# nanoHC06Rx.net
KiCad netlist of a schematic drawn in EAGLE
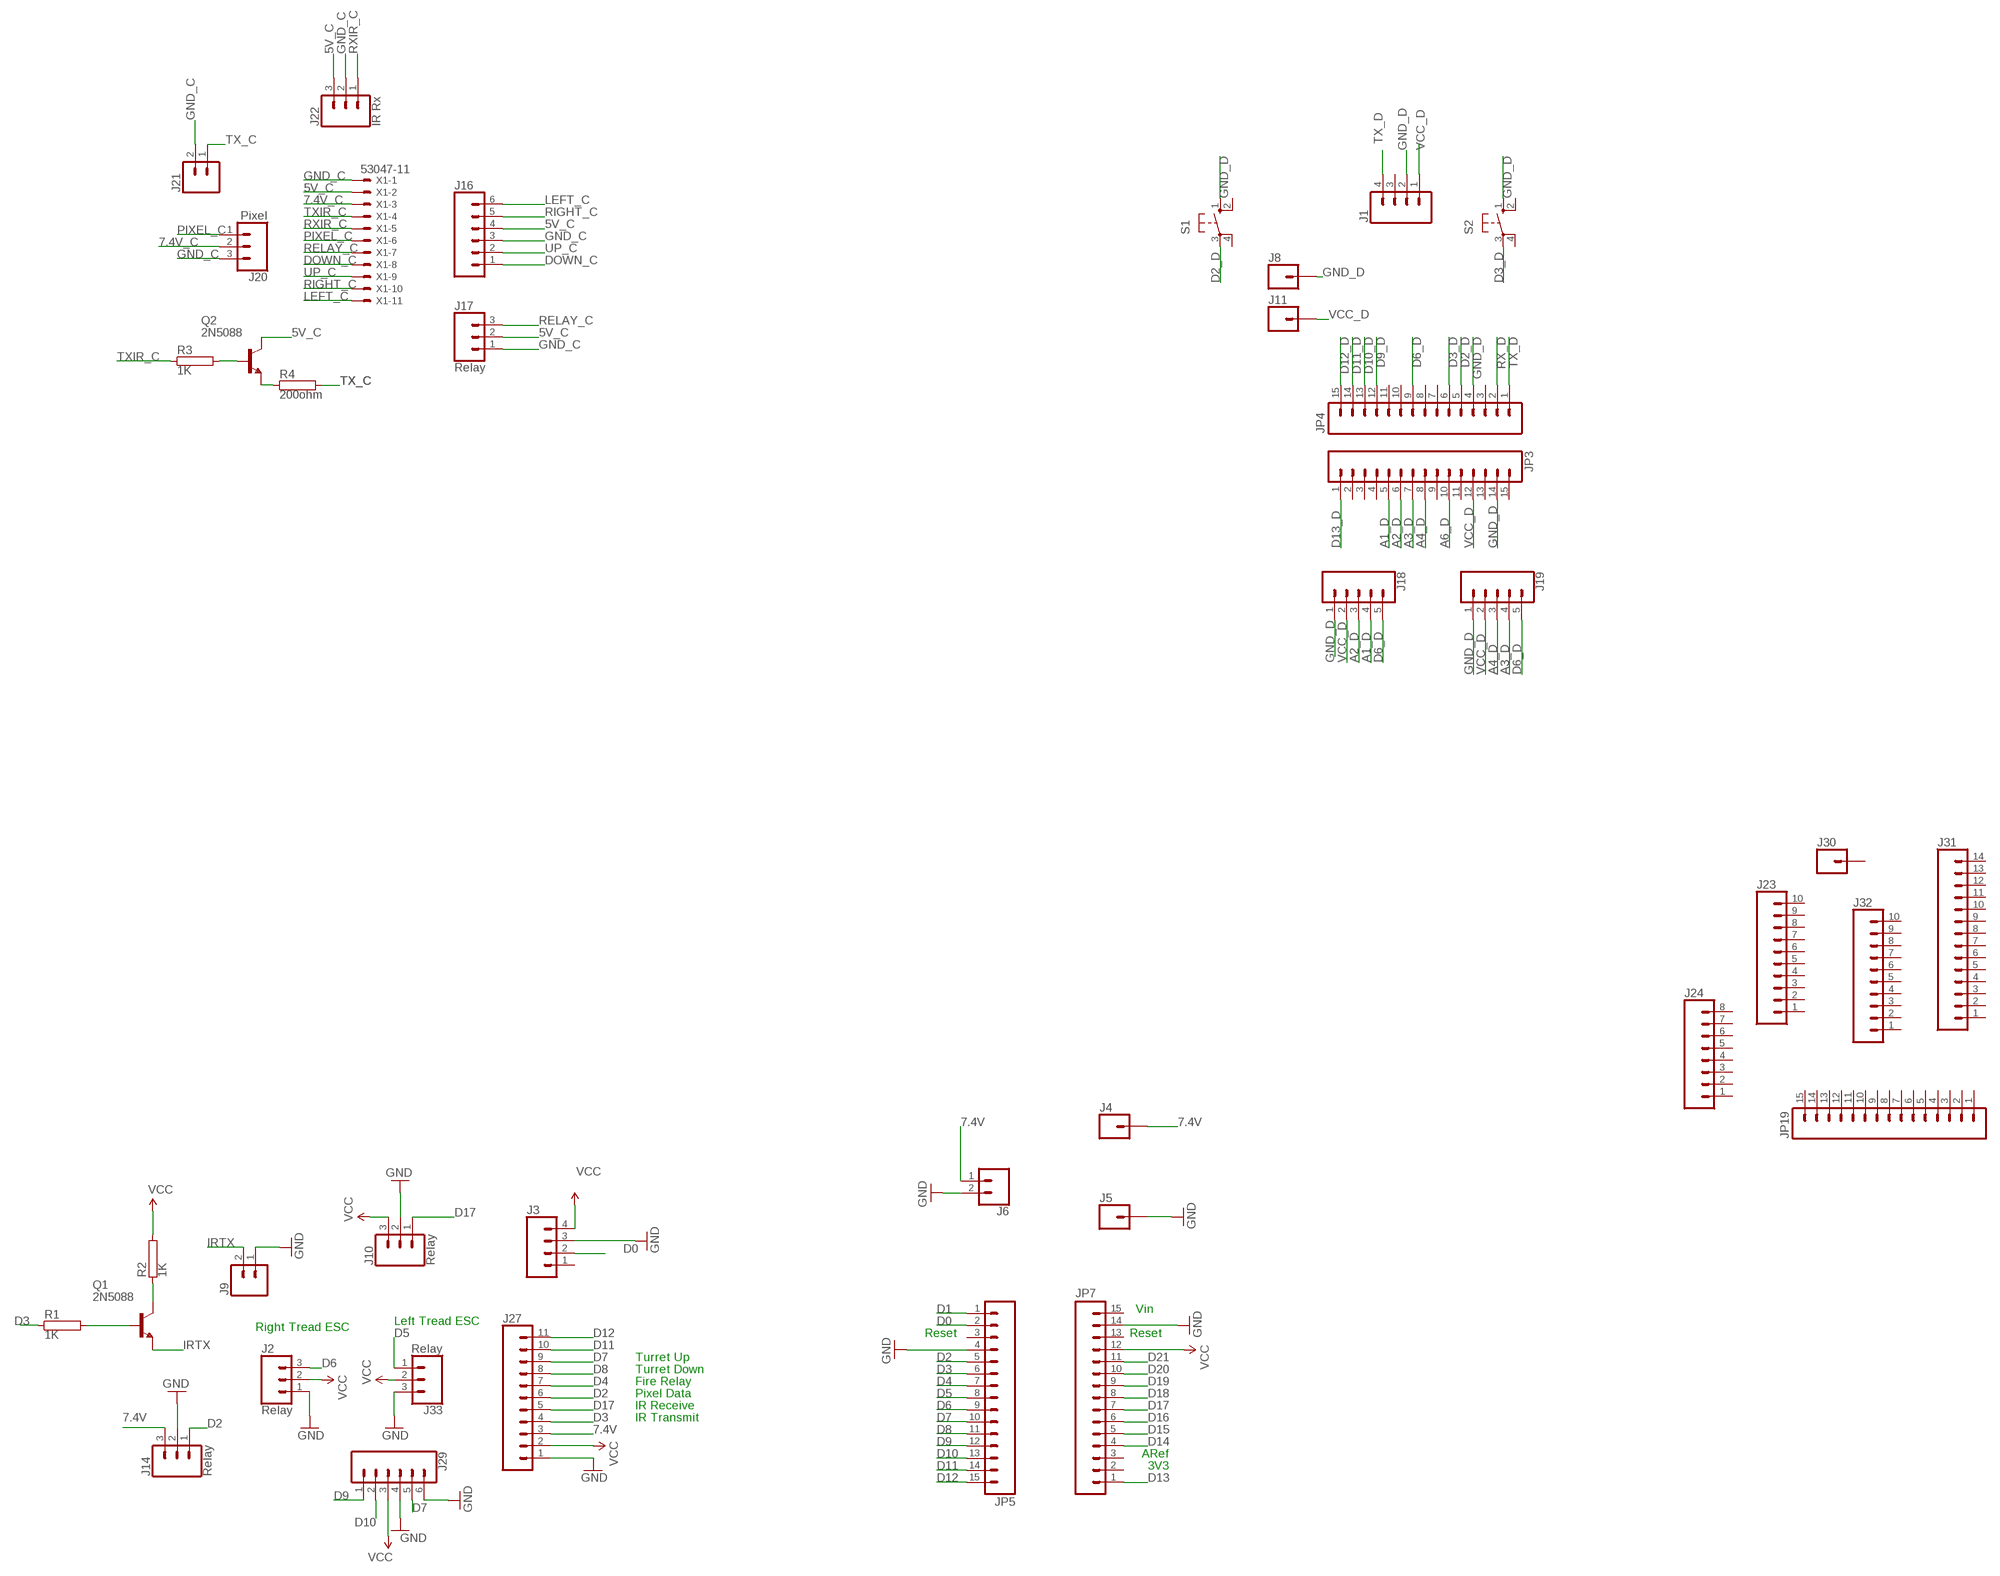
[diagram p0: schematic, sheet 1]

(export (version "E")
  (design (tool "Eeschema 10.0.6"))
  (components
    (comp (ref "J1")
      (value "CONN_04")
      (footprint "eagle-import:1X04")
      (libsource (lib "eagle-import") (part "SparkFun-Connectors_513_CONN_04"))
    )
    (comp (ref "J2")
      (value "Relay")
      (footprint "eagle-import:1X03")
      (libsource (lib "eagle-import") (part "CONN_03"))
    )
    (comp (ref "J3")
      (value "CONN_04")
      (footprint "eagle-import:1X04")
      (libsource (lib "eagle-import") (part "CONN_04"))
    )
    (comp (ref "J4")
      (value "CONN_01")
      (footprint "eagle-import:1X01")
      (libsource (lib "eagle-import") (part "CONN_01"))
    )
    (comp (ref "J5")
      (value "CONN_01")
      (footprint "eagle-import:1X01")
      (libsource (lib "eagle-import") (part "CONN_01"))
    )
    (comp (ref "J6")
      (value "CONN_02")
      (footprint "eagle-import:1X02")
      (libsource (lib "eagle-import") (part "CONN_02"))
    )
    (comp (ref "J8")
      (value "CONN_01")
      (footprint "eagle-import:1X01")
      (libsource (lib "eagle-import") (part "CONN_01"))
    )
    (comp (ref "J9")
      (value "CONN_02")
      (footprint "eagle-import:1X02")
      (libsource (lib "eagle-import") (part "CONN_02"))
    )
    (comp (ref "J10")
      (value "Relay")
      (footprint "eagle-import:1X03")
      (libsource (lib "eagle-import") (part "CONN_03"))
    )
    (comp (ref "J11")
      (value "CONN_01")
      (footprint "eagle-import:1X01")
      (libsource (lib "eagle-import") (part "CONN_01"))
    )
    (comp (ref "J14")
      (value "Relay")
      (footprint "eagle-import:1X03")
      (libsource (lib "eagle-import") (part "CONN_03"))
    )
    (comp (ref "J16")
      (value "CONN_06NO_SILK_FEMALE_PTH")
      (footprint "eagle-import:1X06_NO_SILK")
      (libsource (lib "eagle-import") (part "CONN_06NO_SILK_FEMALE_PTH"))
    )
    (comp (ref "J17")
      (value "Relay")
      (footprint "eagle-import:1X03")
      (libsource (lib "eagle-import") (part "CONN_03"))
    )
    (comp (ref "J18")
      (value "CONN_05")
      (footprint "eagle-import:1X05")
      (libsource (lib "eagle-import") (part "CONN_05"))
    )
    (comp (ref "J19")
      (value "CONN_05")
      (footprint "eagle-import:1X05")
      (libsource (lib "eagle-import") (part "CONN_05"))
    )
    (comp (ref "J20")
      (value "Pixel")
      (footprint "eagle-import:1X03")
      (libsource (lib "eagle-import") (part "CONN_03"))
    )
    (comp (ref "J21")
      (value "CONN_02")
      (footprint "eagle-import:1X02")
      (libsource (lib "eagle-import") (part "CONN_02"))
    )
    (comp (ref "J22")
      (value "IR Rx")
      (footprint "eagle-import:1X03")
      (libsource (lib "eagle-import") (part "CONN_03"))
    )
    (comp (ref "J23")
      (value "CONN_10\"")
      (footprint "eagle-import:1X10")
      (libsource (lib "eagle-import") (part "CONN_10{dblquote}"))
    )
    (comp (ref "J24")
      (value "CONN_08\"")
      (footprint "eagle-import:1X08")
      (libsource (lib "eagle-import") (part "CONN_08{dblquote}"))
    )
    (comp (ref "J27")
      (value "CONN_11")
      (footprint "eagle-import:1X11")
      (libsource (lib "eagle-import") (part "CONN_11"))
    )
    (comp (ref "J29")
      (value "CONN_06NO_SILK_FEMALE_PTH")
      (footprint "eagle-import:1X06_NO_SILK")
      (libsource (lib "eagle-import") (part "CONN_06NO_SILK_FEMALE_PTH"))
    )
    (comp (ref "J30")
      (value "CONN_01")
      (footprint "eagle-import:1X01")
      (libsource (lib "eagle-import") (part "CONN_01"))
    )
    (comp (ref "J31")
      (value "CONN_14")
      (footprint "eagle-import:1X14")
      (libsource (lib "eagle-import") (part "CONN_14"))
    )
    (comp (ref "J32")
      (value "CONN_10\"")
      (footprint "eagle-import:1X10")
      (libsource (lib "eagle-import") (part "CONN_10{dblquote}"))
    )
    (comp (ref "J33")
      (value "Relay")
      (footprint "eagle-import:1X03")
      (libsource (lib "eagle-import") (part "CONN_03"))
    )
    (comp (ref "JP3")
      (value "M15")
      (footprint "eagle-import:1X15@1")
      (libsource (lib "eagle-import") (part "M15"))
    )
    (comp (ref "JP4")
      (value "M15")
      (footprint "eagle-import:1X15@1")
      (libsource (lib "eagle-import") (part "M15"))
    )
    (comp (ref "JP5")
      (value "M15")
      (footprint "eagle-import:1X15@1")
      (libsource (lib "eagle-import") (part "M15"))
    )
    (comp (ref "JP7")
      (value "M15")
      (footprint "eagle-import:1X15@1")
      (libsource (lib "eagle-import") (part "M15"))
    )
    (comp (ref "JP19")
      (value "M15")
      (footprint "eagle-import:1X15@1")
      (libsource (lib "eagle-import") (part "M15"))
    )
    (comp (ref "Q1")
      (value "2N5088")
      (footprint "eagle-import:TO92")
      (libsource (lib "eagle-import") (part "2N5088"))
    )
    (comp (ref "Q2")
      (value "2N5088")
      (footprint "eagle-import:TO92")
      (libsource (lib "eagle-import") (part "2N5088"))
    )
    (comp (ref "R1")
      (value "1K")
      (footprint "eagle-import:CA0001")
      (libsource (lib "eagle-import") (part "RCA0001"))
    )
    (comp (ref "R2")
      (value "1K")
      (footprint "eagle-import:CA0001")
      (libsource (lib "eagle-import") (part "RCA0001"))
    )
    (comp (ref "R3")
      (value "1K")
      (footprint "eagle-import:CA0001")
      (libsource (lib "eagle-import") (part "RCA0001"))
    )
    (comp (ref "R4")
      (value "200ohm")
      (footprint "eagle-import:CA0001")
      (libsource (lib "eagle-import") (part "RCA0001"))
    )
    (comp (ref "S1")
      (value "40-XX")
      (footprint "eagle-import:B3F-40XX")
      (fields (field (name "MF") "OMRON COMPONENTS USA") (field (name "MPN") "B3F-4000"))
      (libsource (lib "eagle-import") (part "40-XX"))
    )
    (comp (ref "S2")
      (value "40-XX")
      (footprint "eagle-import:B3F-40XX")
      (fields (field (name "MF") "OMRON COMPONENTS USA") (field (name "MPN") "B3F-4000"))
      (libsource (lib "eagle-import") (part "40-XX"))
    )
    (comp (ref "X1")
      (value "53047-11")
      (footprint "eagle-import:53047-11")
      (fields (field (name "MF") "WALDOM/MOLEX") (field (name "MPN") "53047-1110"))
      (libsource (lib "eagle-import") (part "53?-11047"))
    )
  )
  (nets
    (net (code "1") (name "/5V_C") (class "Default")
      (node (ref "J16") (pin "4") (pinfunction "4_4") (pintype "passive"))
      (node (ref "J17") (pin "2") (pinfunction "2_2") (pintype "passive"))
      (node (ref "J22") (pin "3") (pinfunction "3_3") (pintype "passive"))
      (node (ref "Q2") (pin "1") (pinfunction "C_1") (pintype "passive"))
      (node (ref "X1") (pin "2") (pinfunction "S_2") (pintype "passive"))
    )
    (net (code "2") (name "/7.4V") (class "Default")
      (node (ref "J14") (pin "3") (pinfunction "3_3") (pintype "passive"))
      (node (ref "J27") (pin "3") (pinfunction "3_3") (pintype "passive"))
      (node (ref "J4") (pin "1") (pinfunction "1_1") (pintype "passive"))
      (node (ref "J6") (pin "1") (pinfunction "1_1") (pintype "passive"))
    )
    (net (code "3") (name "/7.4V_C") (class "Default")
      (node (ref "J20") (pin "2") (pinfunction "2_2") (pintype "passive"))
      (node (ref "X1") (pin "3") (pinfunction "S_3") (pintype "passive"))
    )
    (net (code "4") (name "/A1_D") (class "Default")
      (node (ref "J18") (pin "4") (pinfunction "4_4") (pintype "passive"))
      (node (ref "JP3") (pin "5") (pinfunction "5_5") (pintype "passive"))
    )
    (net (code "5") (name "/A2_D") (class "Default")
      (node (ref "J18") (pin "3") (pinfunction "3_3") (pintype "passive"))
      (node (ref "JP3") (pin "6") (pinfunction "6_6") (pintype "passive"))
    )
    (net (code "6") (name "/A3_D") (class "Default")
      (node (ref "J19") (pin "4") (pinfunction "4_4") (pintype "passive"))
      (node (ref "JP3") (pin "7") (pinfunction "7_7") (pintype "passive"))
    )
    (net (code "7") (name "/A4_D") (class "Default")
      (node (ref "J19") (pin "3") (pinfunction "3_3") (pintype "passive"))
      (node (ref "JP3") (pin "8") (pinfunction "8_8") (pintype "passive"))
    )
    (net (code "8") (name "/A6_D") (class "Default")
      (node (ref "JP3") (pin "10") (pinfunction "10_10") (pintype "passive"))
    )
    (net (code "9") (name "/D0") (class "Default")
      (node (ref "J3") (pin "2") (pinfunction "2_2") (pintype "passive"))
      (node (ref "JP5") (pin "2") (pinfunction "2_2") (pintype "passive"))
    )
    (net (code "10") (name "/D1") (class "Default")
      (node (ref "JP5") (pin "1") (pinfunction "1_1") (pintype "passive"))
    )
    (net (code "11") (name "/D2") (class "Default")
      (node (ref "J14") (pin "1") (pinfunction "1_1") (pintype "passive"))
      (node (ref "J27") (pin "6") (pinfunction "6_6") (pintype "passive"))
      (node (ref "JP5") (pin "5") (pinfunction "5_5") (pintype "passive"))
    )
    (net (code "12") (name "/D2_D") (class "Default")
      (node (ref "JP4") (pin "5") (pinfunction "5_5") (pintype "passive"))
      (node (ref "S1") (pin "3") (pinfunction "P_3") (pintype "passive"))
    )
    (net (code "13") (name "/D3") (class "Default")
      (node (ref "J27") (pin "4") (pinfunction "4_4") (pintype "passive"))
      (node (ref "JP5") (pin "6") (pinfunction "6_6") (pintype "passive"))
      (node (ref "R1") (pin "1") (pinfunction "1_1") (pintype "passive"))
    )
    (net (code "14") (name "/D3_D") (class "Default")
      (node (ref "JP4") (pin "6") (pinfunction "6_6") (pintype "passive"))
      (node (ref "S2") (pin "3") (pinfunction "P_3") (pintype "passive"))
    )
    (net (code "15") (name "/D4") (class "Default")
      (node (ref "J27") (pin "7") (pinfunction "7_7") (pintype "passive"))
      (node (ref "JP5") (pin "7") (pinfunction "7_7") (pintype "passive"))
    )
    (net (code "16") (name "/D5") (class "Default")
      (node (ref "J33") (pin "1") (pinfunction "1_1") (pintype "passive"))
      (node (ref "JP5") (pin "8") (pinfunction "8_8") (pintype "passive"))
    )
    (net (code "17") (name "/D6") (class "Default")
      (node (ref "J2") (pin "3") (pinfunction "3_3") (pintype "passive"))
      (node (ref "JP5") (pin "9") (pinfunction "9_9") (pintype "passive"))
    )
    (net (code "18") (name "/D6_D") (class "Default")
      (node (ref "J18") (pin "5") (pinfunction "5_5") (pintype "passive"))
      (node (ref "J19") (pin "5") (pinfunction "5_5") (pintype "passive"))
      (node (ref "JP4") (pin "9") (pinfunction "9_9") (pintype "passive"))
    )
    (net (code "19") (name "/D7") (class "Default")
      (node (ref "J27") (pin "9") (pinfunction "9_9") (pintype "passive"))
      (node (ref "J29") (pin "5") (pinfunction "5_5") (pintype "passive"))
      (node (ref "JP5") (pin "10") (pinfunction "10_10") (pintype "passive"))
    )
    (net (code "20") (name "/D8") (class "Default")
      (node (ref "J27") (pin "8") (pinfunction "8_8") (pintype "passive"))
      (node (ref "JP5") (pin "11") (pinfunction "11_11") (pintype "passive"))
    )
    (net (code "21") (name "/D9") (class "Default")
      (node (ref "J29") (pin "1") (pinfunction "1_1") (pintype "passive"))
      (node (ref "JP5") (pin "12") (pinfunction "12_12") (pintype "passive"))
    )
    (net (code "22") (name "/D9_D") (class "Default")
      (node (ref "JP4") (pin "12") (pinfunction "12_12") (pintype "passive"))
    )
    (net (code "23") (name "/D10") (class "Default")
      (node (ref "J29") (pin "2") (pinfunction "2_2") (pintype "passive"))
      (node (ref "JP5") (pin "13") (pinfunction "13_13") (pintype "passive"))
    )
    (net (code "24") (name "/D10_D") (class "Default")
      (node (ref "JP4") (pin "13") (pinfunction "13_13") (pintype "passive"))
    )
    (net (code "25") (name "/D11") (class "Default")
      (node (ref "J27") (pin "10") (pinfunction "10_10") (pintype "passive"))
      (node (ref "JP5") (pin "14") (pinfunction "14_14") (pintype "passive"))
    )
    (net (code "26") (name "/D11_D") (class "Default")
      (node (ref "JP4") (pin "14") (pinfunction "14_14") (pintype "passive"))
    )
    (net (code "27") (name "/D12") (class "Default")
      (node (ref "J27") (pin "11") (pinfunction "11_11") (pintype "passive"))
      (node (ref "JP5") (pin "15") (pinfunction "15_15") (pintype "passive"))
    )
    (net (code "28") (name "/D12_D") (class "Default")
      (node (ref "JP4") (pin "15") (pinfunction "15_15") (pintype "passive"))
    )
    (net (code "29") (name "/D13") (class "Default")
      (node (ref "JP7") (pin "1") (pinfunction "1_1") (pintype "passive"))
    )
    (net (code "30") (name "/D13_D") (class "Default")
      (node (ref "JP3") (pin "1") (pinfunction "1_1") (pintype "passive"))
    )
    (net (code "31") (name "/D14") (class "Default")
      (node (ref "JP7") (pin "4") (pinfunction "4_4") (pintype "passive"))
    )
    (net (code "32") (name "/D15") (class "Default")
      (node (ref "JP7") (pin "5") (pinfunction "5_5") (pintype "passive"))
    )
    (net (code "33") (name "/D16") (class "Default")
      (node (ref "JP7") (pin "6") (pinfunction "6_6") (pintype "passive"))
    )
    (net (code "34") (name "/D17") (class "Default")
      (node (ref "J10") (pin "1") (pinfunction "1_1") (pintype "passive"))
      (node (ref "J27") (pin "5") (pinfunction "5_5") (pintype "passive"))
      (node (ref "JP7") (pin "7") (pinfunction "7_7") (pintype "passive"))
    )
    (net (code "35") (name "/D18") (class "Default")
      (node (ref "JP7") (pin "8") (pinfunction "8_8") (pintype "passive"))
    )
    (net (code "36") (name "/D19") (class "Default")
      (node (ref "JP7") (pin "9") (pinfunction "9_9") (pintype "passive"))
    )
    (net (code "37") (name "/D20") (class "Default")
      (node (ref "JP7") (pin "10") (pinfunction "10_10") (pintype "passive"))
    )
    (net (code "38") (name "/D21") (class "Default")
      (node (ref "JP7") (pin "11") (pinfunction "11_11") (pintype "passive"))
    )
    (net (code "39") (name "/DOWN_C") (class "Default")
      (node (ref "J16") (pin "1") (pinfunction "1_1") (pintype "passive"))
      (node (ref "X1") (pin "8") (pinfunction "S_8") (pintype "passive"))
    )
    (net (code "40") (name "/GND_C") (class "Default")
      (node (ref "J16") (pin "3") (pinfunction "3_3") (pintype "passive"))
      (node (ref "J17") (pin "1") (pinfunction "1_1") (pintype "passive"))
      (node (ref "J20") (pin "3") (pinfunction "3_3") (pintype "passive"))
      (node (ref "J21") (pin "2") (pinfunction "2_2") (pintype "passive"))
      (node (ref "J22") (pin "2") (pinfunction "2_2") (pintype "passive"))
      (node (ref "X1") (pin "1") (pinfunction "S_1") (pintype "passive"))
    )
    (net (code "41") (name "/GND_D") (class "Default")
      (node (ref "J1") (pin "2") (pinfunction "2_2") (pintype "passive"))
      (node (ref "J18") (pin "1") (pinfunction "1_1") (pintype "passive"))
      (node (ref "J19") (pin "1") (pinfunction "1_1") (pintype "passive"))
      (node (ref "J8") (pin "1") (pinfunction "1_1") (pintype "passive"))
      (node (ref "JP3") (pin "14") (pinfunction "14_14") (pintype "passive"))
      (node (ref "JP4") (pin "4") (pinfunction "4_4") (pintype "passive"))
      (node (ref "S1") (pin "1") (pinfunction "S_1") (pintype "passive"))
      (node (ref "S2") (pin "1") (pinfunction "S_1") (pintype "passive"))
    )
    (net (code "42") (name "/IRTX") (class "Default")
      (node (ref "J9") (pin "2") (pinfunction "2_2") (pintype "passive"))
      (node (ref "Q1") (pin "3") (pinfunction "E_3") (pintype "passive"))
    )
    (net (code "43") (name "/LEFT_C") (class "Default")
      (node (ref "J16") (pin "6") (pinfunction "6_6") (pintype "passive"))
      (node (ref "X1") (pin "11") (pinfunction "S_11") (pintype "passive"))
    )
    (net (code "44") (name "/PIXEL_C") (class "Default")
      (node (ref "J20") (pin "1") (pinfunction "1_1") (pintype "passive"))
      (node (ref "X1") (pin "6") (pinfunction "S_6") (pintype "passive"))
    )
    (net (code "45") (name "/RELAY_C") (class "Default")
      (node (ref "J17") (pin "3") (pinfunction "3_3") (pintype "passive"))
      (node (ref "X1") (pin "7") (pinfunction "S_7") (pintype "passive"))
    )
    (net (code "46") (name "/RIGHT_C") (class "Default")
      (node (ref "J16") (pin "5") (pinfunction "5_5") (pintype "passive"))
      (node (ref "X1") (pin "10") (pinfunction "S_10") (pintype "passive"))
    )
    (net (code "47") (name "/RXIR_C") (class "Default")
      (node (ref "J22") (pin "1") (pinfunction "1_1") (pintype "passive"))
      (node (ref "X1") (pin "5") (pinfunction "S_5") (pintype "passive"))
    )
    (net (code "48") (name "/RX_D") (class "Default")
      (node (ref "JP4") (pin "2") (pinfunction "2_2") (pintype "passive"))
    )
    (net (code "49") (name "/TXIR_C") (class "Default")
      (node (ref "R3") (pin "1") (pinfunction "1_1") (pintype "passive"))
      (node (ref "X1") (pin "4") (pinfunction "S_4") (pintype "passive"))
    )
    (net (code "50") (name "/TX_C") (class "Default")
      (node (ref "J21") (pin "1") (pinfunction "1_1") (pintype "passive"))
      (node (ref "R4") (pin "2") (pinfunction "2_2") (pintype "passive"))
    )
    (net (code "51") (name "/TX_D") (class "Default")
      (node (ref "J1") (pin "4") (pinfunction "4_4") (pintype "passive"))
      (node (ref "JP4") (pin "1") (pinfunction "1_1") (pintype "passive"))
    )
    (net (code "52") (name "/UP_C") (class "Default")
      (node (ref "J16") (pin "2") (pinfunction "2_2") (pintype "passive"))
      (node (ref "X1") (pin "9") (pinfunction "S_9") (pintype "passive"))
    )
    (net (code "53") (name "/VCC_D") (class "Default")
      (node (ref "J1") (pin "1") (pinfunction "1_1") (pintype "passive"))
      (node (ref "J11") (pin "1") (pinfunction "1_1") (pintype "passive"))
      (node (ref "J18") (pin "2") (pinfunction "2_2") (pintype "passive"))
      (node (ref "J19") (pin "2") (pinfunction "2_2") (pintype "passive"))
      (node (ref "JP3") (pin "12") (pinfunction "12_12") (pintype "passive"))
    )
    (net (code "54") (name "GND") (class "Default")
      (node (ref "J10") (pin "2") (pinfunction "2_2") (pintype "passive"))
      (node (ref "J14") (pin "2") (pinfunction "2_2") (pintype "passive"))
      (node (ref "J2") (pin "1") (pinfunction "1_1") (pintype "passive"))
      (node (ref "J27") (pin "1") (pinfunction "1_1") (pintype "passive"))
      (node (ref "J29") (pin "4") (pinfunction "4_4") (pintype "passive"))
      (node (ref "J29") (pin "6") (pinfunction "6_6") (pintype "passive"))
      (node (ref "J3") (pin "3") (pinfunction "3_3") (pintype "passive"))
      (node (ref "J33") (pin "3") (pinfunction "3_3") (pintype "passive"))
      (node (ref "J5") (pin "1") (pinfunction "1_1") (pintype "passive"))
      (node (ref "J6") (pin "2") (pinfunction "2_2") (pintype "passive"))
      (node (ref "J9") (pin "1") (pinfunction "1_1") (pintype "passive"))
      (node (ref "JP5") (pin "4") (pinfunction "4_4") (pintype "passive"))
      (node (ref "JP7") (pin "14") (pinfunction "14_14") (pintype "passive"))
    )
    (net (code "55") (name "Net-(Q1-B)") (class "Default")
      (node (ref "Q1") (pin "2") (pinfunction "B_2") (pintype "passive"))
      (node (ref "R1") (pin "2") (pinfunction "2_2") (pintype "passive"))
    )
    (net (code "56") (name "Net-(Q1-C)") (class "Default")
      (node (ref "Q1") (pin "1") (pinfunction "C_1") (pintype "passive"))
      (node (ref "R2") (pin "1") (pinfunction "1_1") (pintype "passive"))
    )
    (net (code "57") (name "Net-(Q2-B)") (class "Default")
      (node (ref "Q2") (pin "2") (pinfunction "B_2") (pintype "passive"))
      (node (ref "R3") (pin "2") (pinfunction "2_2") (pintype "passive"))
    )
    (net (code "58") (name "Net-(Q2-E)") (class "Default")
      (node (ref "Q2") (pin "3") (pinfunction "E_3") (pintype "passive"))
      (node (ref "R4") (pin "1") (pinfunction "1_1") (pintype "passive"))
    )
    (net (code "59") (name "VCC") (class "Default")
      (node (ref "J10") (pin "3") (pinfunction "3_3") (pintype "passive"))
      (node (ref "J2") (pin "2") (pinfunction "2_2") (pintype "passive"))
      (node (ref "J27") (pin "2") (pinfunction "2_2") (pintype "passive"))
      (node (ref "J29") (pin "3") (pinfunction "3_3") (pintype "passive"))
      (node (ref "J3") (pin "4") (pinfunction "4_4") (pintype "passive"))
      (node (ref "J33") (pin "2") (pinfunction "2_2") (pintype "passive"))
      (node (ref "JP7") (pin "12") (pinfunction "12_12") (pintype "passive"))
      (node (ref "R2") (pin "2") (pinfunction "2_2") (pintype "passive"))
    )
    (net (code "60") (name "unconnected-(J1-Pad3)") (class "Default")
      (node (ref "J1") (pin "3") (pinfunction "3_3") (pintype "passive"))
    )
    (net (code "61") (name "unconnected-(J3-Pad1)") (class "Default")
      (node (ref "J3") (pin "1") (pinfunction "1_1") (pintype "passive"))
    )
    (net (code "62") (name "unconnected-(J23-Pad1)") (class "Default")
      (node (ref "J23") (pin "1") (pinfunction "1_1") (pintype "passive"))
    )
    (net (code "63") (name "unconnected-(J23-Pad2)") (class "Default")
      (node (ref "J23") (pin "2") (pinfunction "2_2") (pintype "passive"))
    )
    (net (code "64") (name "unconnected-(J23-Pad3)") (class "Default")
      (node (ref "J23") (pin "3") (pinfunction "3_3") (pintype "passive"))
    )
    (net (code "65") (name "unconnected-(J23-Pad4)") (class "Default")
      (node (ref "J23") (pin "4") (pinfunction "4_4") (pintype "passive"))
    )
    (net (code "66") (name "unconnected-(J23-Pad5)") (class "Default")
      (node (ref "J23") (pin "5") (pinfunction "5_5") (pintype "passive"))
    )
    (net (code "67") (name "unconnected-(J23-Pad6)") (class "Default")
      (node (ref "J23") (pin "6") (pinfunction "6_6") (pintype "passive"))
    )
    (net (code "68") (name "unconnected-(J23-Pad7)") (class "Default")
      (node (ref "J23") (pin "7") (pinfunction "7_7") (pintype "passive"))
    )
    (net (code "69") (name "unconnected-(J23-Pad8)") (class "Default")
      (node (ref "J23") (pin "8") (pinfunction "8_8") (pintype "passive"))
    )
    (net (code "70") (name "unconnected-(J23-Pad9)") (class "Default")
      (node (ref "J23") (pin "9") (pinfunction "9_9") (pintype "passive"))
    )
    (net (code "71") (name "unconnected-(J23-Pad10)") (class "Default")
      (node (ref "J23") (pin "10") (pinfunction "10_10") (pintype "passive"))
    )
    (net (code "72") (name "unconnected-(J24-Pad1)") (class "Default")
      (node (ref "J24") (pin "1") (pinfunction "1_1") (pintype "passive"))
    )
    (net (code "73") (name "unconnected-(J24-Pad2)") (class "Default")
      (node (ref "J24") (pin "2") (pinfunction "2_2") (pintype "passive"))
    )
    (net (code "74") (name "unconnected-(J24-Pad3)") (class "Default")
      (node (ref "J24") (pin "3") (pinfunction "3_3") (pintype "passive"))
    )
    (net (code "75") (name "unconnected-(J24-Pad4)") (class "Default")
      (node (ref "J24") (pin "4") (pinfunction "4_4") (pintype "passive"))
    )
    (net (code "76") (name "unconnected-(J24-Pad5)") (class "Default")
      (node (ref "J24") (pin "5") (pinfunction "5_5") (pintype "passive"))
    )
    (net (code "77") (name "unconnected-(J24-Pad6)") (class "Default")
      (node (ref "J24") (pin "6") (pinfunction "6_6") (pintype "passive"))
    )
    (net (code "78") (name "unconnected-(J24-Pad7)") (class "Default")
      (node (ref "J24") (pin "7") (pinfunction "7_7") (pintype "passive"))
    )
    (net (code "79") (name "unconnected-(J24-Pad8)") (class "Default")
      (node (ref "J24") (pin "8") (pinfunction "8_8") (pintype "passive"))
    )
    (net (code "80") (name "unconnected-(J30-Pad1)") (class "Default")
      (node (ref "J30") (pin "1") (pinfunction "1_1") (pintype "passive"))
    )
    (net (code "81") (name "unconnected-(J31-Pad1)") (class "Default")
      (node (ref "J31") (pin "1") (pinfunction "1_1") (pintype "passive"))
    )
    (net (code "82") (name "unconnected-(J31-Pad2)") (class "Default")
      (node (ref "J31") (pin "2") (pinfunction "2_2") (pintype "passive"))
    )
    (net (code "83") (name "unconnected-(J31-Pad3)") (class "Default")
      (node (ref "J31") (pin "3") (pinfunction "3_3") (pintype "passive"))
    )
    (net (code "84") (name "unconnected-(J31-Pad4)") (class "Default")
      (node (ref "J31") (pin "4") (pinfunction "4_4") (pintype "passive"))
    )
    (net (code "85") (name "unconnected-(J31-Pad5)") (class "Default")
      (node (ref "J31") (pin "5") (pinfunction "5_5") (pintype "passive"))
    )
    (net (code "86") (name "unconnected-(J31-Pad6)") (class "Default")
      (node (ref "J31") (pin "6") (pinfunction "6_6") (pintype "passive"))
    )
    (net (code "87") (name "unconnected-(J31-Pad7)") (class "Default")
      (node (ref "J31") (pin "7") (pinfunction "7_7") (pintype "passive"))
    )
    (net (code "88") (name "unconnected-(J31-Pad8)") (class "Default")
      (node (ref "J31") (pin "8") (pinfunction "8_8") (pintype "passive"))
    )
    (net (code "89") (name "unconnected-(J31-Pad9)") (class "Default")
      (node (ref "J31") (pin "9") (pinfunction "9_9") (pintype "passive"))
    )
    (net (code "90") (name "unconnected-(J31-Pad10)") (class "Default")
      (node (ref "J31") (pin "10") (pinfunction "10_10") (pintype "passive"))
    )
    (net (code "91") (name "unconnected-(J31-Pad11)") (class "Default")
      (node (ref "J31") (pin "11") (pinfunction "11_11") (pintype "passive"))
    )
    (net (code "92") (name "unconnected-(J31-Pad12)") (class "Default")
      (node (ref "J31") (pin "12") (pinfunction "12_12") (pintype "passive"))
    )
    (net (code "93") (name "unconnected-(J31-Pad13)") (class "Default")
      (node (ref "J31") (pin "13") (pinfunction "13_13") (pintype "passive"))
    )
    (net (code "94") (name "unconnected-(J31-Pad14)") (class "Default")
      (node (ref "J31") (pin "14") (pinfunction "14_14") (pintype "passive"))
    )
    (net (code "95") (name "unconnected-(J32-Pad1)") (class "Default")
      (node (ref "J32") (pin "1") (pinfunction "1_1") (pintype "passive"))
    )
    (net (code "96") (name "unconnected-(J32-Pad2)") (class "Default")
      (node (ref "J32") (pin "2") (pinfunction "2_2") (pintype "passive"))
    )
    (net (code "97") (name "unconnected-(J32-Pad3)") (class "Default")
      (node (ref "J32") (pin "3") (pinfunction "3_3") (pintype "passive"))
    )
    (net (code "98") (name "unconnected-(J32-Pad4)") (class "Default")
      (node (ref "J32") (pin "4") (pinfunction "4_4") (pintype "passive"))
    )
    (net (code "99") (name "unconnected-(J32-Pad5)") (class "Default")
      (node (ref "J32") (pin "5") (pinfunction "5_5") (pintype "passive"))
    )
    (net (code "100") (name "unconnected-(J32-Pad6)") (class "Default")
      (node (ref "J32") (pin "6") (pinfunction "6_6") (pintype "passive"))
    )
    (net (code "101") (name "unconnected-(J32-Pad7)") (class "Default")
      (node (ref "J32") (pin "7") (pinfunction "7_7") (pintype "passive"))
    )
    (net (code "102") (name "unconnected-(J32-Pad8)") (class "Default")
      (node (ref "J32") (pin "8") (pinfunction "8_8") (pintype "passive"))
    )
    (net (code "103") (name "unconnected-(J32-Pad9)") (class "Default")
      (node (ref "J32") (pin "9") (pinfunction "9_9") (pintype "passive"))
    )
    (net (code "104") (name "unconnected-(J32-Pad10)") (class "Default")
      (node (ref "J32") (pin "10") (pinfunction "10_10") (pintype "passive"))
    )
    (net (code "105") (name "unconnected-(JP3-Pad2)") (class "Default")
      (node (ref "JP3") (pin "2") (pinfunction "2_2") (pintype "passive"))
    )
    (net (code "106") (name "unconnected-(JP3-Pad3)") (class "Default")
      (node (ref "JP3") (pin "3") (pinfunction "3_3") (pintype "passive"))
    )
    (net (code "107") (name "unconnected-(JP3-Pad4)") (class "Default")
      (node (ref "JP3") (pin "4") (pinfunction "4_4") (pintype "passive"))
    )
    (net (code "108") (name "unconnected-(JP3-Pad9)") (class "Default")
      (node (ref "JP3") (pin "9") (pinfunction "9_9") (pintype "passive"))
    )
    (net (code "109") (name "unconnected-(JP3-Pad11)") (class "Default")
      (node (ref "JP3") (pin "11") (pinfunction "11_11") (pintype "passive"))
    )
    (net (code "110") (name "unconnected-(JP3-Pad13)") (class "Default")
      (node (ref "JP3") (pin "13") (pinfunction "13_13") (pintype "passive"))
    )
    (net (code "111") (name "unconnected-(JP3-Pad15)") (class "Default")
      (node (ref "JP3") (pin "15") (pinfunction "15_15") (pintype "passive"))
    )
    (net (code "112") (name "unconnected-(JP4-Pad3)") (class "Default")
      (node (ref "JP4") (pin "3") (pinfunction "3_3") (pintype "passive"))
    )
    (net (code "113") (name "unconnected-(JP4-Pad7)") (class "Default")
      (node (ref "JP4") (pin "7") (pinfunction "7_7") (pintype "passive"))
    )
    (net (code "114") (name "unconnected-(JP4-Pad8)") (class "Default")
      (node (ref "JP4") (pin "8") (pinfunction "8_8") (pintype "passive"))
    )
    (net (code "115") (name "unconnected-(JP4-Pad10)") (class "Default")
      (node (ref "JP4") (pin "10") (pinfunction "10_10") (pintype "passive"))
    )
    (net (code "116") (name "unconnected-(JP4-Pad11)") (class "Default")
      (node (ref "JP4") (pin "11") (pinfunction "11_11") (pintype "passive"))
    )
    (net (code "117") (name "unconnected-(JP5-Pad3)") (class "Default")
      (node (ref "JP5") (pin "3") (pinfunction "3_3") (pintype "passive"))
    )
    (net (code "118") (name "unconnected-(JP7-Pad2)") (class "Default")
      (node (ref "JP7") (pin "2") (pinfunction "2_2") (pintype "passive"))
    )
    (net (code "119") (name "unconnected-(JP7-Pad3)") (class "Default")
      (node (ref "JP7") (pin "3") (pinfunction "3_3") (pintype "passive"))
    )
    (net (code "120") (name "unconnected-(JP7-Pad13)") (class "Default")
      (node (ref "JP7") (pin "13") (pinfunction "13_13") (pintype "passive"))
    )
    (net (code "121") (name "unconnected-(JP7-Pad15)") (class "Default")
      (node (ref "JP7") (pin "15") (pinfunction "15_15") (pintype "passive"))
    )
    (net (code "122") (name "unconnected-(JP19-Pad1)") (class "Default")
      (node (ref "JP19") (pin "1") (pinfunction "1_1") (pintype "passive"))
    )
    (net (code "123") (name "unconnected-(JP19-Pad2)") (class "Default")
      (node (ref "JP19") (pin "2") (pinfunction "2_2") (pintype "passive"))
    )
    (net (code "124") (name "unconnected-(JP19-Pad3)") (class "Default")
      (node (ref "JP19") (pin "3") (pinfunction "3_3") (pintype "passive"))
    )
    (net (code "125") (name "unconnected-(JP19-Pad4)") (class "Default")
      (node (ref "JP19") (pin "4") (pinfunction "4_4") (pintype "passive"))
    )
    (net (code "126") (name "unconnected-(JP19-Pad5)") (class "Default")
      (node (ref "JP19") (pin "5") (pinfunction "5_5") (pintype "passive"))
    )
    (net (code "127") (name "unconnected-(JP19-Pad6)") (class "Default")
      (node (ref "JP19") (pin "6") (pinfunction "6_6") (pintype "passive"))
    )
    (net (code "128") (name "unconnected-(JP19-Pad7)") (class "Default")
      (node (ref "JP19") (pin "7") (pinfunction "7_7") (pintype "passive"))
    )
    (net (code "129") (name "unconnected-(JP19-Pad8)") (class "Default")
      (node (ref "JP19") (pin "8") (pinfunction "8_8") (pintype "passive"))
    )
    (net (code "130") (name "unconnected-(JP19-Pad9)") (class "Default")
      (node (ref "JP19") (pin "9") (pinfunction "9_9") (pintype "passive"))
    )
    (net (code "131") (name "unconnected-(JP19-Pad10)") (class "Default")
      (node (ref "JP19") (pin "10") (pinfunction "10_10") (pintype "passive"))
    )
    (net (code "132") (name "unconnected-(JP19-Pad11)") (class "Default")
      (node (ref "JP19") (pin "11") (pinfunction "11_11") (pintype "passive"))
    )
    (net (code "133") (name "unconnected-(JP19-Pad12)") (class "Default")
      (node (ref "JP19") (pin "12") (pinfunction "12_12") (pintype "passive"))
    )
    (net (code "134") (name "unconnected-(JP19-Pad13)") (class "Default")
      (node (ref "JP19") (pin "13") (pinfunction "13_13") (pintype "passive"))
    )
    (net (code "135") (name "unconnected-(JP19-Pad14)") (class "Default")
      (node (ref "JP19") (pin "14") (pinfunction "14_14") (pintype "passive"))
    )
    (net (code "136") (name "unconnected-(JP19-Pad15)") (class "Default")
      (node (ref "JP19") (pin "15") (pinfunction "15_15") (pintype "passive"))
    )
    (net (code "137") (name "unconnected-(S1-P1-Pad4)") (class "Default")
      (node (ref "S1") (pin "4") (pinfunction "P1_4") (pintype "passive"))
    )
    (net (code "138") (name "unconnected-(S1-S1-Pad2)") (class "Default")
      (node (ref "S1") (pin "2") (pinfunction "S1_2") (pintype "passive"))
    )
    (net (code "139") (name "unconnected-(S2-P1-Pad4)") (class "Default")
      (node (ref "S2") (pin "4") (pinfunction "P1_4") (pintype "passive"))
    )
    (net (code "140") (name "unconnected-(S2-S1-Pad2)") (class "Default")
      (node (ref "S2") (pin "2") (pinfunction "S1_2") (pintype "passive"))
    )
  )
)
